# Digital.net
KiCad netlist of a schematic drawn in Altium Designer
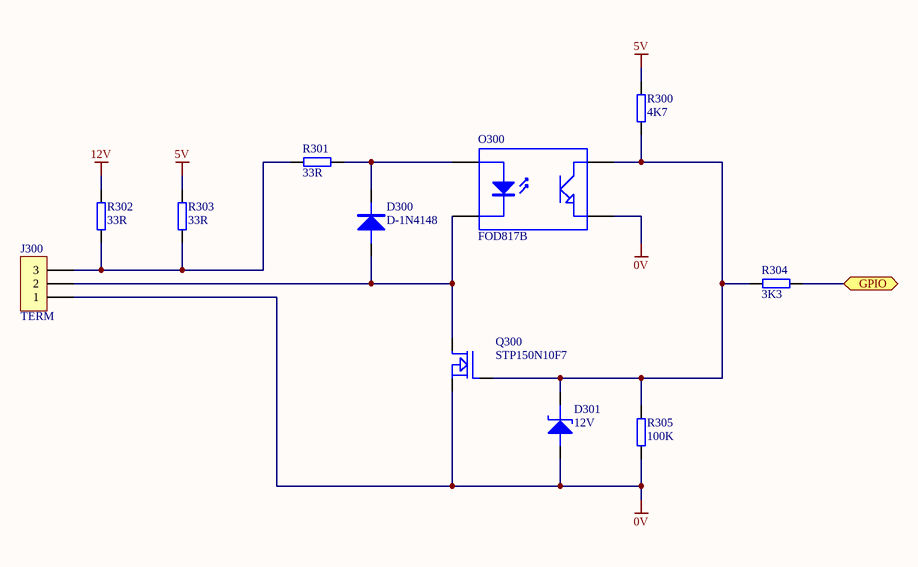
[diagram p0: Digital.SchDoc]

(export (version "E")
  (design (tool "Eeschema 10.0.6"))
  (components
    (comp (ref "D300")
      (value "D-1N4148")
      (footprint "DO35S")
      (description "1N4148")
      (libsource (lib "SSR") (part "D-1N4148"))
    )
    (comp (ref "D301")
      (value "12V")
      (footprint "DO35S")
      (description "ZENER DIODE")
      (libsource (lib "SSR") (part "D-BZX79-12"))
    )
    (comp (ref "J300")
      (value "TERM")
      (footprint "MKD500S3")
      (description "CONNECTOR")
      (libsource (lib "SSR") (part "J-SCR-3"))
    )
    (comp (ref "O300")
      (value "FOD817B")
      (footprint "DIP4")
      (description "OPTO ISOLATOR")
      (libsource (lib "SSR") (part "O-FOD817B"))
    )
    (comp (ref "Q300")
      (value "STP150N10F7")
      (footprint "TO220FS")
      (description "MOSFET")
      (libsource (lib "SSR") (part "Q-STP150N10F7"))
    )
    (comp (ref "R300")
      (value "4K7")
      (footprint "AXIAL04")
      (description "RESISTOR")
      (libsource (lib "SSR") (part "R-A4K7"))
    )
    (comp (ref "R301")
      (value "33R")
      (footprint "AXIAL04")
      (description "RESISTOR")
      (libsource (lib "SSR") (part "R-A33R"))
    )
    (comp (ref "R302")
      (value "33R")
      (footprint "AXIAL04")
      (description "RESISTOR")
      (libsource (lib "SSR") (part "R-A33R"))
    )
    (comp (ref "R303")
      (value "33R")
      (footprint "AXIAL04")
      (description "RESISTOR")
      (libsource (lib "SSR") (part "R-A33R"))
    )
    (comp (ref "R304")
      (value "3K3")
      (footprint "AXIAL04")
      (description "RESISTOR")
      (libsource (lib "SSR") (part "R-A3K3"))
    )
    (comp (ref "R305")
      (value "100K")
      (footprint "AXIAL04")
      (description "RESISTOR")
      (libsource (lib "SSR") (part "R-A100K"))
    )
  )
  (nets
    (net (code "1") (name "/GPIO") (class "Default")
      (node (ref "R304") (pin "2") (pinfunction "2_2") (pintype "passive"))
    )
    (net (code "2") (name "0V") (class "Default")
      (node (ref "D301") (pin "1") (pinfunction "A_1") (pintype "passive"))
      (node (ref "J300") (pin "1") (pinfunction "1_1") (pintype "passive"))
      (node (ref "O300") (pin "3") (pinfunction "E_3") (pintype "passive"))
      (node (ref "Q300") (pin "3") (pinfunction "S_3") (pintype "passive"))
      (node (ref "R305") (pin "1") (pinfunction "1_1") (pintype "passive"))
    )
    (net (code "3") (name "5V") (class "Default")
      (node (ref "R300") (pin "2") (pinfunction "2_2") (pintype "passive"))
      (node (ref "R303") (pin "2") (pinfunction "2_2") (pintype "passive"))
    )
    (net (code "4") (name "12V") (class "Default")
      (node (ref "R302") (pin "2") (pinfunction "2_2") (pintype "passive"))
    )
    (net (code "5") (name "Net-(D300-A)") (class "Default")
      (node (ref "D300") (pin "1") (pinfunction "A_1") (pintype "passive"))
      (node (ref "J300") (pin "2") (pinfunction "2_2") (pintype "passive"))
      (node (ref "O300") (pin "2") (pinfunction "K_2") (pintype "passive"))
      (node (ref "Q300") (pin "2") (pinfunction "D_2") (pintype "passive"))
    )
    (net (code "6") (name "Net-(D300-K)") (class "Default")
      (node (ref "D300") (pin "2") (pinfunction "K_2") (pintype "passive"))
      (node (ref "O300") (pin "1") (pinfunction "A_1") (pintype "passive"))
      (node (ref "R301") (pin "1") (pinfunction "1_1") (pintype "passive"))
    )
    (net (code "7") (name "Net-(D301-K)") (class "Default")
      (node (ref "D301") (pin "2") (pinfunction "K_2") (pintype "passive"))
      (node (ref "O300") (pin "4") (pinfunction "C_4") (pintype "passive"))
      (node (ref "Q300") (pin "1") (pinfunction "G_1") (pintype "passive"))
      (node (ref "R300") (pin "1") (pinfunction "1_1") (pintype "passive"))
      (node (ref "R304") (pin "1") (pinfunction "1_1") (pintype "passive"))
      (node (ref "R305") (pin "2") (pinfunction "2_2") (pintype "passive"))
    )
    (net (code "8") (name "Net-(J300-Pad3)") (class "Default")
      (node (ref "J300") (pin "3") (pinfunction "3_3") (pintype "passive"))
      (node (ref "R301") (pin "2") (pinfunction "2_2") (pintype "passive"))
      (node (ref "R302") (pin "1") (pinfunction "1_1") (pintype "passive"))
      (node (ref "R303") (pin "1") (pinfunction "1_1") (pintype "passive"))
    )
  )
)
